# 18f4550.net
KiCad netlist of a schematic drawn in Altium Designer
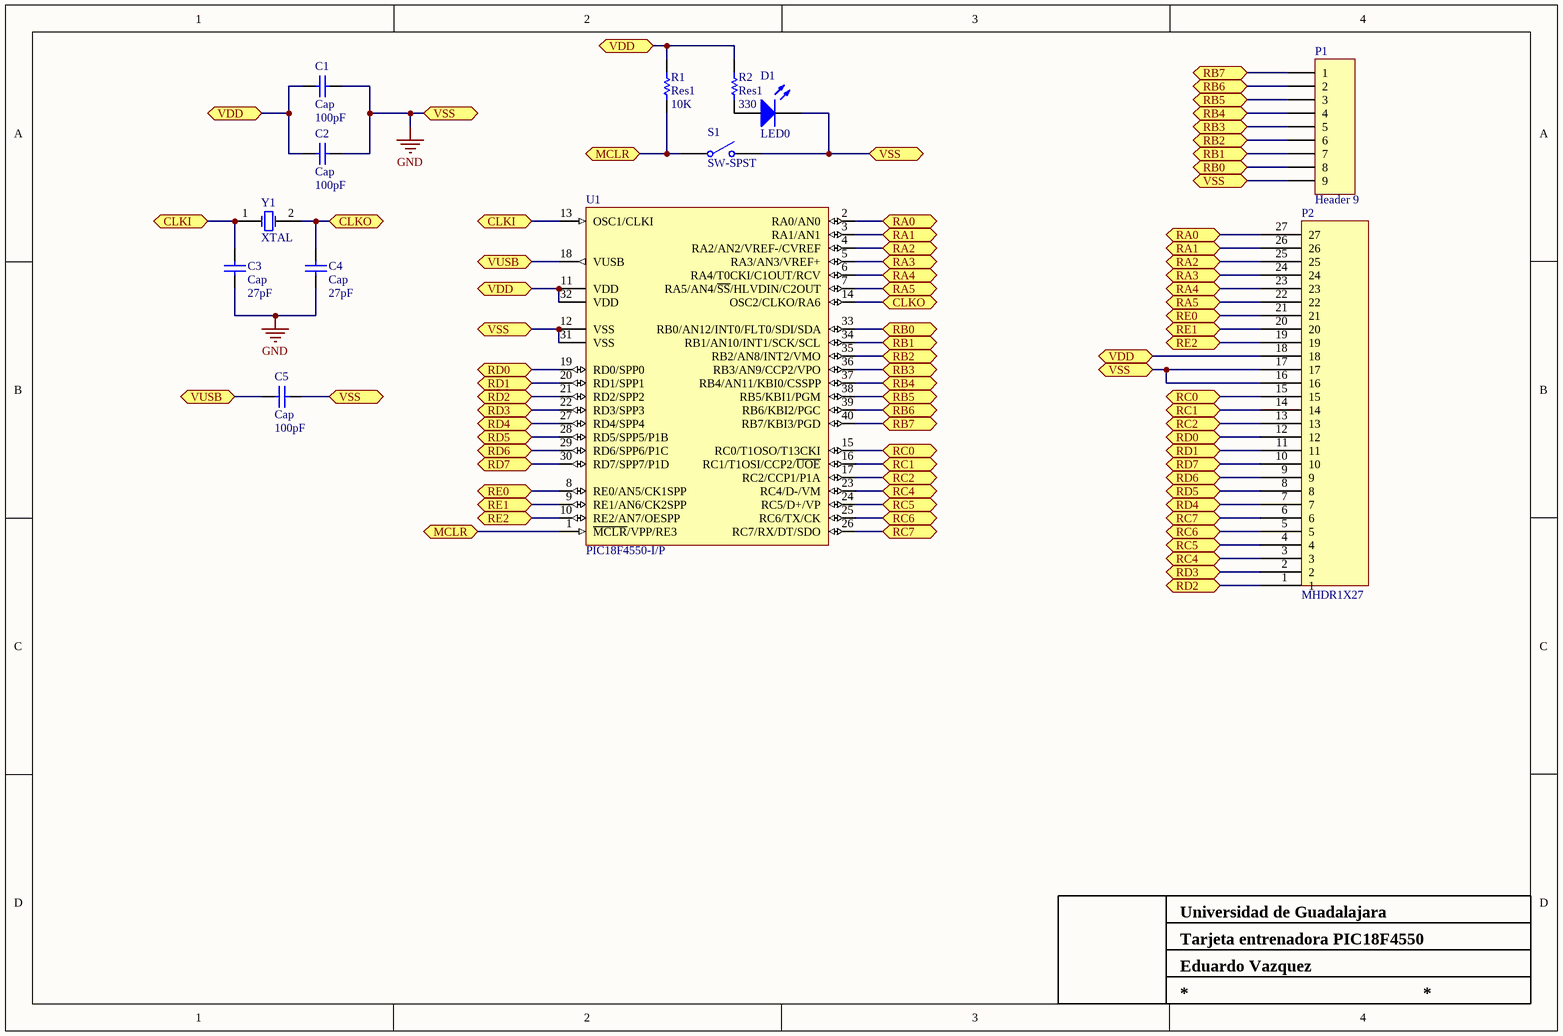
[diagram p0: 18f4550.SchDoc]

(export (version "E")
  (design (tool "Eeschema 10.0.6"))
  (components
    (comp (ref "C1")
      (value "Cap")
      (footprint "CAP-CER1")
      (description "Capacitor")
      (fields (field (name "ALTIUM_VALUE") "100pF") (field (name "PUBLISHER") "Altium Limited"))
      (libsource (lib "Miscellaneous Devices") (part "Cap"))
    )
    (comp (ref "C2")
      (value "Cap")
      (footprint "CAP-CER1")
      (description "Capacitor")
      (fields (field (name "ALTIUM_VALUE") "100pF") (field (name "PUBLISHER") "Altium Limited"))
      (libsource (lib "Miscellaneous Devices") (part "Cap"))
    )
    (comp (ref "C3")
      (value "Cap")
      (footprint "CAP-CER2")
      (description "Capacitor")
      (fields (field (name "ALTIUM_VALUE") "27pF") (field (name "PUBLISHER") "Altium Limited"))
      (libsource (lib "Miscellaneous Devices") (part "Cap"))
    )
    (comp (ref "C4")
      (value "Cap")
      (footprint "CAP-CER2")
      (description "Capacitor")
      (fields (field (name "ALTIUM_VALUE") "27pF") (field (name "PUBLISHER") "Altium Limited"))
      (libsource (lib "Miscellaneous Devices") (part "Cap"))
    )
    (comp (ref "C5")
      (value "Cap")
      (footprint "CAP-CER1")
      (description "Capacitor")
      (fields (field (name "ALTIUM_VALUE") "100pF") (field (name "PUBLISHER") "Altium Limited"))
      (libsource (lib "Miscellaneous Devices") (part "Cap"))
    )
    (comp (ref "D1")
      (value "LED0")
      (footprint "LED-3MM")
      (description "Typical INFRARED GaAs LED")
      (fields (field (name "PUBLISHER") "Altium Limited"))
      (libsource (lib "Miscellaneous Devices") (part "LED0"))
    )
    (comp (ref "P1")
      (value "Header 9")
      (footprint "HDR1X9")
      (description "Header, 9-Pin")
      (fields (field (name "PUBLISHER") "Altium Limited"))
      (libsource (lib "Miscellaneous Connectors") (part "Header 9"))
    )
    (comp (ref "P2") (value "MHDR1X27") (footprint "MHDR1X27") (libsource (lib "HEADER27") (part "MHDR1X27")))
    (comp (ref "R1")
      (value "Res1")
      (footprint "AXIAL-0.3")
      (description "Resistor")
      (fields (field (name "ALTIUM_VALUE") "10K") (field (name "PUBLISHER") "Altium Limited"))
      (libsource (lib "Miscellaneous Devices") (part "Res1"))
    )
    (comp (ref "R2")
      (value "Res1")
      (footprint "AXIAL-0.3")
      (description "Resistor")
      (fields (field (name "ALTIUM_VALUE") "330") (field (name "PUBLISHER") "Altium Limited"))
      (libsource (lib "Miscellaneous Devices") (part "Res1"))
    )
    (comp (ref "S1")
      (value "SW-SPST")
      (footprint "SW-SPST-SIL")
      (description "Single-Pole, Single-Throw Switch")
      (fields (field (name "PUBLISHER") "Altium Limited"))
      (libsource (lib "Miscellaneous Devices") (part "SW-SPST"))
    )
    (comp (ref "U1")
      (value "PIC18F4550-I/P")
      (footprint "4550")
      (fields (field (name "PUBLISHER") "Altium Limited"))
      (libsource (lib "Microchip Microcontroller 8-Bit PIC18") (part "PIC18F4550-I/P"))
    )
    (comp (ref "Y1")
      (value "XTAL")
      (footprint "XTAL")
      (description "Crystal Oscillator")
      (fields (field (name "PUBLISHER") "Altium Limited"))
      (libsource (lib "Miscellaneous Devices") (part "XTAL"))
    )
  )
  (nets
    (net (code "1") (name "/CLKI") (class "Default")
      (node (ref "C3") (pin "1") (pinfunction "1_1") (pintype "passive"))
      (node (ref "U1") (pin "13") (pinfunction "OSC1/CLKI_13") (pintype "input"))
      (node (ref "Y1") (pin "1") (pinfunction "OSC1_1") (pintype "passive"))
    )
    (net (code "2") (name "/CLKO") (class "Default")
      (node (ref "C4") (pin "1") (pinfunction "1_1") (pintype "passive"))
      (node (ref "U1") (pin "14") (pinfunction "OSC2/CLKO/RA6_14") (pintype "bidirectional"))
      (node (ref "Y1") (pin "2") (pinfunction "OSC2_2") (pintype "passive"))
    )
    (net (code "3") (name "/MCLR") (class "Default")
      (node (ref "R1") (pin "1") (pinfunction "1_1") (pintype "passive"))
      (node (ref "S1") (pin "1") (pinfunction "COMMON_1") (pintype "passive"))
      (node (ref "U1") (pin "1") (pinfunction "~{MCLR}/VPP/RE3_1") (pintype "input"))
    )
    (net (code "4") (name "/RA0") (class "Default")
      (node (ref "P2") (pin "27") (pinfunction "27_27") (pintype "passive"))
      (node (ref "U1") (pin "2") (pinfunction "RA0/AN0_2") (pintype "bidirectional"))
    )
    (net (code "5") (name "/RA1") (class "Default")
      (node (ref "P2") (pin "26") (pinfunction "26_26") (pintype "passive"))
      (node (ref "U1") (pin "3") (pinfunction "RA1/AN1_3") (pintype "bidirectional"))
    )
    (net (code "6") (name "/RA2") (class "Default")
      (node (ref "P2") (pin "25") (pinfunction "25_25") (pintype "passive"))
      (node (ref "U1") (pin "4") (pinfunction "RA2/AN2/VREF-/CVREF_4") (pintype "bidirectional"))
    )
    (net (code "7") (name "/RA3") (class "Default")
      (node (ref "P2") (pin "24") (pinfunction "24_24") (pintype "passive"))
      (node (ref "U1") (pin "5") (pinfunction "RA3/AN3/VREF+_5") (pintype "bidirectional"))
    )
    (net (code "8") (name "/RA4") (class "Default")
      (node (ref "P2") (pin "23") (pinfunction "23_23") (pintype "passive"))
      (node (ref "U1") (pin "6") (pinfunction "RA4/T0CKI/C1OUT/RCV_6") (pintype "bidirectional"))
    )
    (net (code "9") (name "/RA5") (class "Default")
      (node (ref "P2") (pin "22") (pinfunction "22_22") (pintype "passive"))
      (node (ref "U1") (pin "7") (pinfunction "RA5/AN4/~{SS}/HLVDIN/C2OUT_7") (pintype "bidirectional"))
    )
    (net (code "10") (name "/RB0") (class "Default")
      (node (ref "P1") (pin "8") (pinfunction "8_8") (pintype "passive"))
      (node (ref "U1") (pin "33") (pinfunction "RB0/AN12/INT0/FLT0/SDI/SDA_33") (pintype "bidirectional"))
    )
    (net (code "11") (name "/RB1") (class "Default")
      (node (ref "P1") (pin "7") (pinfunction "7_7") (pintype "passive"))
      (node (ref "U1") (pin "34") (pinfunction "RB1/AN10/INT1/SCK/SCL_34") (pintype "bidirectional"))
    )
    (net (code "12") (name "/RB2") (class "Default")
      (node (ref "P1") (pin "6") (pinfunction "6_6") (pintype "passive"))
      (node (ref "U1") (pin "35") (pinfunction "RB2/AN8/INT2/VMO_35") (pintype "bidirectional"))
    )
    (net (code "13") (name "/RB3") (class "Default")
      (node (ref "P1") (pin "5") (pinfunction "5_5") (pintype "passive"))
      (node (ref "U1") (pin "36") (pinfunction "RB3/AN9/CCP2/VPO_36") (pintype "bidirectional"))
    )
    (net (code "14") (name "/RB4") (class "Default")
      (node (ref "P1") (pin "4") (pinfunction "4_4") (pintype "passive"))
      (node (ref "U1") (pin "37") (pinfunction "RB4/AN11/KBI0/CSSPP_37") (pintype "bidirectional"))
    )
    (net (code "15") (name "/RB5") (class "Default")
      (node (ref "P1") (pin "3") (pinfunction "3_3") (pintype "passive"))
      (node (ref "U1") (pin "38") (pinfunction "RB5/KBI1/PGM_38") (pintype "bidirectional"))
    )
    (net (code "16") (name "/RB6") (class "Default")
      (node (ref "P1") (pin "2") (pinfunction "2_2") (pintype "passive"))
      (node (ref "U1") (pin "39") (pinfunction "RB6/KBI2/PGC_39") (pintype "bidirectional"))
    )
    (net (code "17") (name "/RB7") (class "Default")
      (node (ref "P1") (pin "1") (pinfunction "1_1") (pintype "passive"))
      (node (ref "U1") (pin "40") (pinfunction "RB7/KBI3/PGD_40") (pintype "bidirectional"))
    )
    (net (code "18") (name "/RC0") (class "Default")
      (node (ref "P2") (pin "15") (pinfunction "15_15") (pintype "passive"))
      (node (ref "U1") (pin "15") (pinfunction "RC0/T1OSO/T13CKI_15") (pintype "bidirectional"))
    )
    (net (code "19") (name "/RC1") (class "Default")
      (node (ref "P2") (pin "14") (pinfunction "14_14") (pintype "passive"))
      (node (ref "U1") (pin "16") (pinfunction "RC1/T1OSI/CCP2/~{UOE}_16") (pintype "bidirectional"))
    )
    (net (code "20") (name "/RC2") (class "Default")
      (node (ref "P2") (pin "13") (pinfunction "13_13") (pintype "passive"))
      (node (ref "U1") (pin "17") (pinfunction "RC2/CCP1/P1A_17") (pintype "bidirectional"))
    )
    (net (code "21") (name "/RC4") (class "Default")
      (node (ref "P2") (pin "3") (pinfunction "3_3") (pintype "passive"))
      (node (ref "U1") (pin "23") (pinfunction "RC4/D-/VM_23") (pintype "bidirectional"))
    )
    (net (code "22") (name "/RC5") (class "Default")
      (node (ref "P2") (pin "4") (pinfunction "4_4") (pintype "passive"))
      (node (ref "U1") (pin "24") (pinfunction "RC5/D+/VP_24") (pintype "bidirectional"))
    )
    (net (code "23") (name "/RC6") (class "Default")
      (node (ref "P2") (pin "5") (pinfunction "5_5") (pintype "passive"))
      (node (ref "U1") (pin "25") (pinfunction "RC6/TX/CK_25") (pintype "bidirectional"))
    )
    (net (code "24") (name "/RC7") (class "Default")
      (node (ref "P2") (pin "6") (pinfunction "6_6") (pintype "passive"))
      (node (ref "U1") (pin "26") (pinfunction "RC7/RX/DT/SDO_26") (pintype "bidirectional"))
    )
    (net (code "25") (name "/RD0") (class "Default")
      (node (ref "P2") (pin "12") (pinfunction "12_12") (pintype "passive"))
      (node (ref "U1") (pin "19") (pinfunction "RD0/SPP0_19") (pintype "bidirectional"))
    )
    (net (code "26") (name "/RD1") (class "Default")
      (node (ref "P2") (pin "11") (pinfunction "11_11") (pintype "passive"))
      (node (ref "U1") (pin "20") (pinfunction "RD1/SPP1_20") (pintype "bidirectional"))
    )
    (net (code "27") (name "/RD2") (class "Default")
      (node (ref "P2") (pin "1") (pinfunction "1_1") (pintype "passive"))
      (node (ref "U1") (pin "21") (pinfunction "RD2/SPP2_21") (pintype "bidirectional"))
    )
    (net (code "28") (name "/RD3") (class "Default")
      (node (ref "P2") (pin "2") (pinfunction "2_2") (pintype "passive"))
      (node (ref "U1") (pin "22") (pinfunction "RD3/SPP3_22") (pintype "bidirectional"))
    )
    (net (code "29") (name "/RD4") (class "Default")
      (node (ref "P2") (pin "7") (pinfunction "7_7") (pintype "passive"))
      (node (ref "U1") (pin "27") (pinfunction "RD4/SPP4_27") (pintype "bidirectional"))
    )
    (net (code "30") (name "/RD5") (class "Default")
      (node (ref "P2") (pin "8") (pinfunction "8_8") (pintype "passive"))
      (node (ref "U1") (pin "28") (pinfunction "RD5/SPP5/P1B_28") (pintype "bidirectional"))
    )
    (net (code "31") (name "/RD6") (class "Default")
      (node (ref "P2") (pin "9") (pinfunction "9_9") (pintype "passive"))
      (node (ref "U1") (pin "29") (pinfunction "RD6/SPP6/P1C_29") (pintype "bidirectional"))
    )
    (net (code "32") (name "/RD7") (class "Default")
      (node (ref "P2") (pin "10") (pinfunction "10_10") (pintype "passive"))
      (node (ref "U1") (pin "30") (pinfunction "RD7/SPP7/P1D_30") (pintype "bidirectional"))
    )
    (net (code "33") (name "/RE0") (class "Default")
      (node (ref "P2") (pin "21") (pinfunction "21_21") (pintype "passive"))
      (node (ref "U1") (pin "8") (pinfunction "RE0/AN5/CK1SPP_8") (pintype "bidirectional"))
    )
    (net (code "34") (name "/RE1") (class "Default")
      (node (ref "P2") (pin "20") (pinfunction "20_20") (pintype "passive"))
      (node (ref "U1") (pin "9") (pinfunction "RE1/AN6/CK2SPP_9") (pintype "bidirectional"))
    )
    (net (code "35") (name "/RE2") (class "Default")
      (node (ref "P2") (pin "19") (pinfunction "19_19") (pintype "passive"))
      (node (ref "U1") (pin "10") (pinfunction "RE2/AN7/OESPP_10") (pintype "bidirectional"))
    )
    (net (code "36") (name "/VDD") (class "Default")
      (node (ref "C1") (pin "1") (pinfunction "1_1") (pintype "passive"))
      (node (ref "C2") (pin "1") (pinfunction "1_1") (pintype "passive"))
      (node (ref "P2") (pin "18") (pinfunction "18_18") (pintype "passive"))
      (node (ref "R1") (pin "2") (pinfunction "2_2") (pintype "passive"))
      (node (ref "R2") (pin "2") (pinfunction "2_2") (pintype "passive"))
      (node (ref "U1") (pin "11") (pinfunction "VDD_11") (pintype "power_in"))
      (node (ref "U1") (pin "32") (pinfunction "VDD_32") (pintype "power_in"))
    )
    (net (code "37") (name "/VUSB") (class "Default")
      (node (ref "C5") (pin "1") (pinfunction "1_1") (pintype "passive"))
      (node (ref "U1") (pin "18") (pinfunction "VUSB_18") (pintype "output"))
    )
    (net (code "38") (name "GND") (class "Default")
      (node (ref "C1") (pin "2") (pinfunction "2_2") (pintype "passive"))
      (node (ref "C2") (pin "2") (pinfunction "2_2") (pintype "passive"))
      (node (ref "C3") (pin "2") (pinfunction "2_2") (pintype "passive"))
      (node (ref "C4") (pin "2") (pinfunction "2_2") (pintype "passive"))
      (node (ref "C5") (pin "2") (pinfunction "2_2") (pintype "passive"))
      (node (ref "D1") (pin "2") (pinfunction "K_2") (pintype "passive"))
      (node (ref "P1") (pin "9") (pinfunction "9_9") (pintype "passive"))
      (node (ref "P2") (pin "16") (pinfunction "16_16") (pintype "passive"))
      (node (ref "P2") (pin "17") (pinfunction "17_17") (pintype "passive"))
      (node (ref "S1") (pin "2") (pinfunction "NO_2") (pintype "passive"))
      (node (ref "U1") (pin "12") (pinfunction "VSS_12") (pintype "power_in"))
      (node (ref "U1") (pin "31") (pinfunction "VSS_31") (pintype "power_in"))
    )
    (net (code "39") (name "Net-(D1-A)") (class "Default")
      (node (ref "D1") (pin "1") (pinfunction "A_1") (pintype "passive"))
      (node (ref "R2") (pin "1") (pinfunction "1_1") (pintype "passive"))
    )
  )
)
